# Deel_5_display.net
KiCad netlist of a schematic drawn in Altium Designer
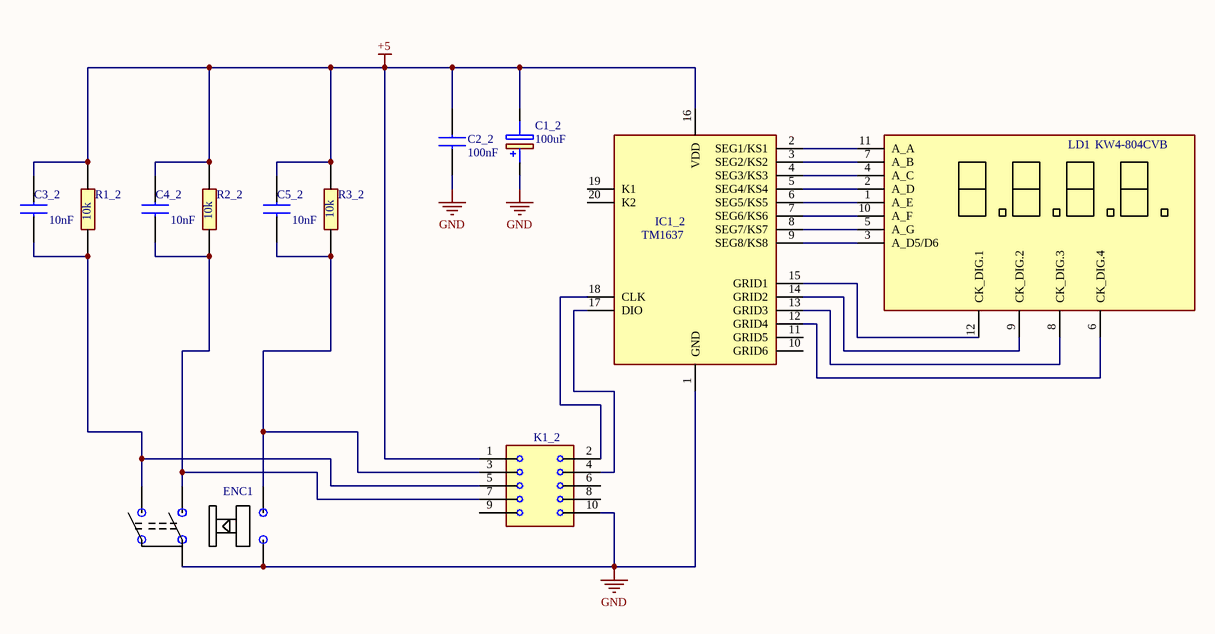
[diagram p0: Deel_5_display.SchDoc]

(export (version "E")
  (design (tool "Eeschema 10.0.6"))
  (components
    (comp (ref "C1_2")
      (value "100uF")
      (footprint "PcbLib1:100uf")
      (description "Capacitor Polarised RGA101M1HBK-0811G")
      (fields (field (name "MANUFACTURER_PART_NUMBER") "RGA101M1HBK-0811G"))
      (libsource (lib "Schlib_soldeerstation") (part "100uF"))
    )
    (comp (ref "C2_2")
      (value "100nF")
      (footprint "PcbLib1:100nF")
      (description "Capacitor")
      (fields
        (field (name "MANUFACTURER_PART_NUMBER") "0402YC104MAT2A")
        (field (name "MOUSER PART NUMBER") "581-0402YC104MAT2A")
      )
      (libsource (lib "Schlib_soldeerstation") (part "100nF"))
    )
    (comp (ref "C3_2")
      (value "10nF")
      (footprint "PcbLib1:10nF")
      (description "Capacitor")
      (fields
        (field (name "MANUFACTURER_PART_NUMBER") "0402YC104MAT2A")
        (field (name "MOUSER PART NUMBER") "581-0402YC104MAT2A")
      )
      (libsource (lib "Schlib_soldeerstation") (part "10nF"))
    )
    (comp (ref "C4_2")
      (value "10nF")
      (footprint "PcbLib1:10nF")
      (description "Capacitor")
      (fields
        (field (name "MANUFACTURER_PART_NUMBER") "0402YC104MAT2A")
        (field (name "MOUSER PART NUMBER") "581-0402YC104MAT2A")
      )
      (libsource (lib "Schlib_soldeerstation") (part "10nF"))
    )
    (comp (ref "C5_2")
      (value "10nF")
      (footprint "PcbLib1:10nF")
      (description "Capacitor")
      (fields
        (field (name "MANUFACTURER_PART_NUMBER") "0402YC104MAT2A")
        (field (name "MOUSER PART NUMBER") "581-0402YC104MAT2A")
      )
      (libsource (lib "Schlib_soldeerstation") (part "10nF"))
    )
    (comp (ref "ENC1")
      (value "PEC11R-4225F-S0024 encoder")
      (footprint "PcbLib1:PEC11R-4225F-S0024")
      (description "draai encoder met drukknop")
      (fields
        (field (name "MANUFACTURER_PART_NUMBER") "PEC11R-4225F-S0024")
        (field (name "MOUSER PART NUMBER") "652-PEC11R-4225F-S24")
      )
      (libsource (lib "Schlib_soldeerstation") (part "PEC11R-4225F-S0024 encoder"))
    )
    (comp (ref "IC1_2")
      (value "TM1637")
      (footprint "PcbLib1:tm1637")
      (description "Integrated Circuit")
      (fields (field (name "MANUFACTURER_PART_NUMBER") "TM1637 (SOP)"))
      (libsource (lib "Schlib_soldeerstation") (part "TM1637__SOP_"))
    )
    (comp (ref "K1_2")
      (value "10 boxheader")
      (footprint "PcbLib1:10BoxHeader")
      (description "Connector")
      (fields (field (name "MANUFACTURER_PART_NUMBER") "0010897100"))
      (libsource (lib "Schlib_soldeerstation") (part "10 boxheader"))
    )
    (comp (ref "LD1")
      (value "KW4-804CVB")
      (footprint "PcbLib1:kw4")
      (description "Display")
      (libsource (lib "Schlib_soldeerstation") (part "KW4-804CVB"))
    )
    (comp (ref "R1_2")
      (value "10k")
      (footprint "PcbLib1:10k")
      (description "Resistor")
      (fields
        (field (name "MANUFACTURER_PART_NUMBER") "CPF0805B100RE1")
        (field (name "MOUSER PART NUMBER") "279-CPF0805B100RE1")
      )
      (libsource (lib "Schlib_soldeerstation") (part "10k"))
    )
    (comp (ref "R2_2")
      (value "10k")
      (footprint "PcbLib1:10k")
      (description "Resistor")
      (fields
        (field (name "MANUFACTURER_PART_NUMBER") "CPF0805B100RE1")
        (field (name "MOUSER PART NUMBER") "279-CPF0805B100RE1")
      )
      (libsource (lib "Schlib_soldeerstation") (part "10k"))
    )
    (comp (ref "R3_2")
      (value "10k")
      (footprint "PcbLib1:10k")
      (description "Resistor")
      (fields
        (field (name "MANUFACTURER_PART_NUMBER") "CPF0805B100RE1")
        (field (name "MOUSER PART NUMBER") "279-CPF0805B100RE1")
      )
      (libsource (lib "Schlib_soldeerstation") (part "10k"))
    )
  )
  (nets
    (net (code "1") (name "+5") (class "Default")
      (node (ref "C1_2") (pin "2") (pinfunction "-_2") (pintype "passive"))
      (node (ref "C2_2") (pin "2") (pinfunction "2_2") (pintype "passive"))
      (node (ref "C3_2") (pin "2") (pinfunction "2_2") (pintype "passive"))
      (node (ref "C4_2") (pin "2") (pinfunction "2_2") (pintype "passive"))
      (node (ref "C5_2") (pin "2") (pinfunction "2_2") (pintype "passive"))
      (node (ref "IC1_2") (pin "16") (pinfunction "VDD_16") (pintype "passive"))
      (node (ref "K1_2") (pin "1") (pinfunction "1_1") (pintype "passive"))
      (node (ref "R1_2") (pin "2") (pinfunction "2_2") (pintype "passive"))
      (node (ref "R2_2") (pin "2") (pinfunction "2_2") (pintype "passive"))
      (node (ref "R3_2") (pin "2") (pinfunction "2_2") (pintype "passive"))
    )
    (net (code "2") (name "GND") (class "Default")
      (node (ref "C1_2") (pin "1") (pinfunction "+_1") (pintype "passive"))
      (node (ref "C2_2") (pin "1") (pinfunction "1_1") (pintype "passive"))
      (node (ref "ENC1") (pin "3") (pinfunction "3_3") (pintype "passive"))
      (node (ref "ENC1") (pin "4") (pinfunction "4_4") (pintype "passive"))
      (node (ref "IC1_2") (pin "1") (pinfunction "GND_1") (pintype "passive"))
      (node (ref "K1_2") (pin "10") (pinfunction "10_10") (pintype "passive"))
    )
    (net (code "3") (name "Net-(C3_2-Pad1)") (class "Default")
      (node (ref "C3_2") (pin "1") (pinfunction "1_1") (pintype "passive"))
      (node (ref "ENC1") (pin "1") (pinfunction "1_1") (pintype "passive"))
      (node (ref "K1_2") (pin "5") (pinfunction "5_5") (pintype "passive"))
      (node (ref "R1_2") (pin "1") (pinfunction "1_1") (pintype "passive"))
    )
    (net (code "4") (name "Net-(C4_2-Pad1)") (class "Default")
      (node (ref "C4_2") (pin "1") (pinfunction "1_1") (pintype "passive"))
      (node (ref "ENC1") (pin "2") (pinfunction "2_2") (pintype "passive"))
      (node (ref "K1_2") (pin "7") (pinfunction "7_7") (pintype "passive"))
      (node (ref "R2_2") (pin "1") (pinfunction "1_1") (pintype "passive"))
    )
    (net (code "5") (name "Net-(C5_2-Pad1)") (class "Default")
      (node (ref "C5_2") (pin "1") (pinfunction "1_1") (pintype "passive"))
      (node (ref "ENC1") (pin "5") (pinfunction "5_5") (pintype "passive"))
      (node (ref "K1_2") (pin "3") (pinfunction "3_3") (pintype "passive"))
      (node (ref "R3_2") (pin "1") (pinfunction "1_1") (pintype "passive"))
    )
    (net (code "6") (name "Net-(IC1_2-CLK)") (class "Default")
      (node (ref "IC1_2") (pin "18") (pinfunction "CLK_18") (pintype "passive"))
      (node (ref "K1_2") (pin "2") (pinfunction "2_2") (pintype "passive"))
    )
    (net (code "7") (name "Net-(IC1_2-DIO)") (class "Default")
      (node (ref "IC1_2") (pin "17") (pinfunction "DIO_17") (pintype "passive"))
      (node (ref "K1_2") (pin "4") (pinfunction "4_4") (pintype "passive"))
    )
    (net (code "8") (name "Net-(IC1_2-GRID1)") (class "Default")
      (node (ref "IC1_2") (pin "15") (pinfunction "GRID1_15") (pintype "passive"))
      (node (ref "LD1") (pin "12") (pinfunction "CK_DIG.1_12") (pintype "passive"))
    )
    (net (code "9") (name "Net-(IC1_2-GRID2)") (class "Default")
      (node (ref "IC1_2") (pin "14") (pinfunction "GRID2_14") (pintype "passive"))
      (node (ref "LD1") (pin "9") (pinfunction "CK_DIG.2_9") (pintype "passive"))
    )
    (net (code "10") (name "Net-(IC1_2-GRID3)") (class "Default")
      (node (ref "IC1_2") (pin "13") (pinfunction "GRID3_13") (pintype "passive"))
      (node (ref "LD1") (pin "8") (pinfunction "CK_DIG.3_8") (pintype "passive"))
    )
    (net (code "11") (name "Net-(IC1_2-GRID4)") (class "Default")
      (node (ref "IC1_2") (pin "12") (pinfunction "GRID4_12") (pintype "passive"))
      (node (ref "LD1") (pin "6") (pinfunction "CK_DIG.4_6") (pintype "passive"))
    )
    (net (code "12") (name "Net-(IC1_2-SEG1{slash}KS1)") (class "Default")
      (node (ref "IC1_2") (pin "2") (pinfunction "SEG1/KS1_2") (pintype "passive"))
      (node (ref "LD1") (pin "11") (pinfunction "A_A_11") (pintype "passive"))
    )
    (net (code "13") (name "Net-(IC1_2-SEG2{slash}KS2)") (class "Default")
      (node (ref "IC1_2") (pin "3") (pinfunction "SEG2/KS2_3") (pintype "passive"))
      (node (ref "LD1") (pin "7") (pinfunction "A_B_7") (pintype "passive"))
    )
    (net (code "14") (name "Net-(IC1_2-SEG3{slash}KS3)") (class "Default")
      (node (ref "IC1_2") (pin "4") (pinfunction "SEG3/KS3_4") (pintype "passive"))
      (node (ref "LD1") (pin "4") (pinfunction "A_C_4") (pintype "passive"))
    )
    (net (code "15") (name "Net-(IC1_2-SEG4{slash}KS4)") (class "Default")
      (node (ref "IC1_2") (pin "5") (pinfunction "SEG4/KS4_5") (pintype "passive"))
      (node (ref "LD1") (pin "2") (pinfunction "A_D_2") (pintype "passive"))
    )
    (net (code "16") (name "Net-(IC1_2-SEG5{slash}KS5)") (class "Default")
      (node (ref "IC1_2") (pin "6") (pinfunction "SEG5/KS5_6") (pintype "passive"))
      (node (ref "LD1") (pin "1") (pinfunction "A_E_1") (pintype "passive"))
    )
    (net (code "17") (name "Net-(IC1_2-SEG6{slash}KS6)") (class "Default")
      (node (ref "IC1_2") (pin "7") (pinfunction "SEG6/KS6_7") (pintype "passive"))
      (node (ref "LD1") (pin "10") (pinfunction "A_F_10") (pintype "passive"))
    )
    (net (code "18") (name "Net-(IC1_2-SEG7{slash}KS7)") (class "Default")
      (node (ref "IC1_2") (pin "8") (pinfunction "SEG7/KS7_8") (pintype "passive"))
      (node (ref "LD1") (pin "5") (pinfunction "A_G_5") (pintype "passive"))
    )
    (net (code "19") (name "Net-(IC1_2-SEG8{slash}KS8)") (class "Default")
      (node (ref "IC1_2") (pin "9") (pinfunction "SEG8/KS8_9") (pintype "passive"))
      (node (ref "LD1") (pin "3") (pinfunction "A_D5/D6_3") (pintype "passive"))
    )
    (net (code "20") (name "unconnected-(IC1_2-GRID5-Pad11)") (class "Default")
      (node (ref "IC1_2") (pin "11") (pinfunction "GRID5_11") (pintype "passive"))
    )
    (net (code "21") (name "unconnected-(IC1_2-GRID6-Pad10)") (class "Default")
      (node (ref "IC1_2") (pin "10") (pinfunction "GRID6_10") (pintype "passive"))
    )
    (net (code "22") (name "unconnected-(IC1_2-K1-Pad19)") (class "Default")
      (node (ref "IC1_2") (pin "19") (pinfunction "K1_19") (pintype "passive"))
    )
    (net (code "23") (name "unconnected-(IC1_2-K2-Pad20)") (class "Default")
      (node (ref "IC1_2") (pin "20") (pinfunction "K2_20") (pintype "passive"))
    )
    (net (code "24") (name "unconnected-(K1_2-Pad6)") (class "Default")
      (node (ref "K1_2") (pin "6") (pinfunction "6_6") (pintype "passive"))
    )
    (net (code "25") (name "unconnected-(K1_2-Pad8)") (class "Default")
      (node (ref "K1_2") (pin "8") (pinfunction "8_8") (pintype "passive"))
    )
    (net (code "26") (name "unconnected-(K1_2-Pad9)") (class "Default")
      (node (ref "K1_2") (pin "9") (pinfunction "9_9") (pintype "passive"))
    )
  )
)
